# 2xSplitter.net
KiCad netlist of a schematic drawn in EAGLE
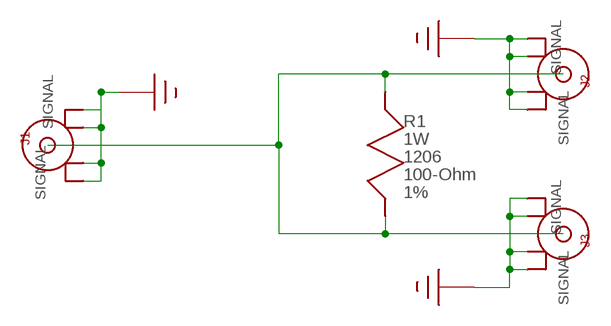
[diagram p0: schematic, sheet 1]

(export (version "E")
  (design (tool "Eeschema 10.0.6"))
  (components
    (comp (ref "J1")
      (value "SMA-END")
      (footprint "eagle-import:SMA-END")
      (fields (field (name "PARTNUM") "ACX1911-ND"))
      (libsource (lib "eagle-import") (part "SMA-END"))
    )
    (comp (ref "J2")
      (value "SMA-END")
      (footprint "eagle-import:SMA-END")
      (fields (field (name "PARTNUM") "ACX1911-ND"))
      (libsource (lib "eagle-import") (part "SMA-END"))
    )
    (comp (ref "J3")
      (value "SMA-END")
      (footprint "eagle-import:SMA-END")
      (fields (field (name "PARTNUM") "ACX1911-ND"))
      (libsource (lib "eagle-import") (part "SMA-END"))
    )
    (comp (ref "R1")
      (value "100-Ohm")
      (footprint "eagle-import:R1206")
      (fields (field (name "TOLERANCE") "1%") (field (name "POWER") "1W") (field (name "SIZE") "1206"))
      (libsource (lib "eagle-import") (part "RESISTOR-R1206"))
    )
  )
  (nets
    (net (code "1") (name "GROUND") (class "Default")
      (node (ref "J1") (pin "P$2") (pinfunction "P$5_P$2") (pintype "bidirectional"))
      (node (ref "J1") (pin "P$3") (pinfunction "P$4_P$3") (pintype "bidirectional"))
      (node (ref "J1") (pin "P$4") (pinfunction "P$3_P$4") (pintype "bidirectional"))
      (node (ref "J1") (pin "P$5") (pinfunction "P$2_P$5") (pintype "bidirectional"))
      (node (ref "J2") (pin "P$2") (pinfunction "P$5_P$2") (pintype "bidirectional"))
      (node (ref "J2") (pin "P$3") (pinfunction "P$4_P$3") (pintype "bidirectional"))
      (node (ref "J2") (pin "P$4") (pinfunction "P$3_P$4") (pintype "bidirectional"))
      (node (ref "J2") (pin "P$5") (pinfunction "P$2_P$5") (pintype "bidirectional"))
      (node (ref "J3") (pin "P$2") (pinfunction "P$5_P$2") (pintype "bidirectional"))
      (node (ref "J3") (pin "P$3") (pinfunction "P$4_P$3") (pintype "bidirectional"))
      (node (ref "J3") (pin "P$4") (pinfunction "P$3_P$4") (pintype "bidirectional"))
      (node (ref "J3") (pin "P$5") (pinfunction "P$2_P$5") (pintype "bidirectional"))
    )
    (net (code "2") (name "Net-(R1-A)") (class "Default")
      (node (ref "J1") (pin "SIGNAL") (pinfunction "SIGNAL_SIGNAL") (pintype "bidirectional"))
      (node (ref "J2") (pin "SIGNAL") (pinfunction "SIGNAL_SIGNAL") (pintype "bidirectional"))
      (node (ref "J3") (pin "SIGNAL") (pinfunction "SIGNAL_SIGNAL") (pintype "bidirectional"))
      (node (ref "R1") (pin "P$1") (pinfunction "A_P$1") (pintype "bidirectional"))
      (node (ref "R1") (pin "P$2") (pinfunction "B_P$2") (pintype "bidirectional"))
    )
  )
)
